# SUP_1_5_3_3.net
KiCad netlist of a schematic drawn in Altium Designer
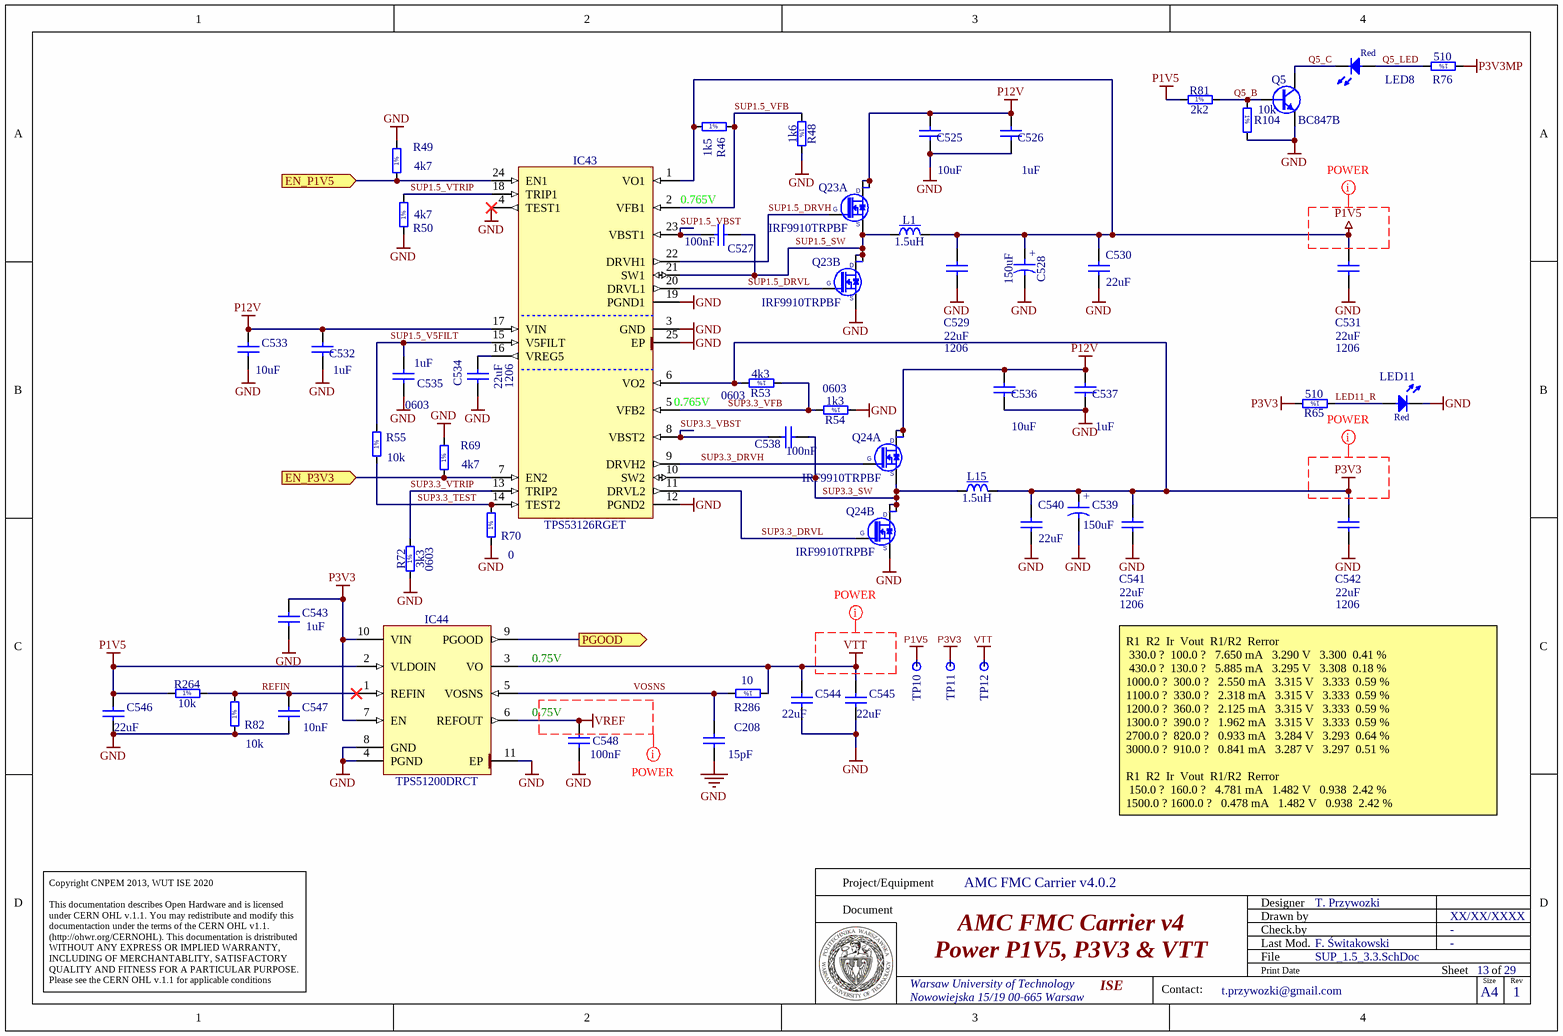
[diagram p0: SUP_1.5_3.3.SchDoc]

(export (version "E")
  (design (tool "Eeschema 10.0.6"))
  (components
    (comp (ref "C208")
      (value "15pF")
      (footprint "CAPC1005X55N")
      (description "Non-polarised capacitor")
      (fields
        (field (name "PART NUMBER") "CC0402_15PF_50V_5%_NP0")
        (field (name "VOLTAGE") "50V")
        (field (name "AUTHOR") "CERN DEM JLC")
      )
      (libsource (lib "Capacitors") (part "Capacitor - non polarized"))
    )
    (comp (ref "C525")
      (value "10uF")
      (footprint "CAPC2012X135N")
      (description "Non-polarised capacitor")
      (fields
        (field (name "PART NUMBER") "CC0805_10UF_16V_10%_X5R")
        (field (name "VOLTAGE") "16V")
        (field (name "AUTHOR") "CERN DEM JLC")
      )
      (libsource (lib "Capacitors") (part "Capacitor - non polarized"))
    )
    (comp (ref "C526")
      (value "1uF")
      (footprint "CAPC1608X87N")
      (description "Non-polarised capacitor")
      (fields
        (field (name "PART NUMBER") "CC0603_1UF_16V_10%_X7R")
        (field (name "VOLTAGE") "16V")
        (field (name "AUTHOR") "CERN DEM JLC")
      )
      (libsource (lib "Capacitors") (part "Capacitor - non polarized"))
    )
    (comp (ref "C527")
      (value "100nF")
      (footprint "CAPC1005X55N")
      (description "Non-polarised capacitor")
      (fields
        (field (name "PART NUMBER") "CC0402_100NF_16V_10%_X7R")
        (field (name "VOLTAGE") "16V")
        (field (name "AUTHOR") "CERN DEM JLC")
      )
      (libsource (lib "Capacitors") (part "Capacitor - non polarized"))
    )
    (comp (ref "C528")
      (value "150uF")
      (footprint "CAPMP7343X200N")
      (description "Polarised capacitor")
      (fields
        (field (name "PART NUMBER") "CAEM7343-20_150UF_4V_20%_LESR0016")
        (field (name "VOLTAGE") "4V")
        (field (name "AUTHOR") "CERN DEM JLC")
      )
      (libsource (lib "Capacitors") (part "Capacitor - polarized"))
    )
    (comp (ref "C529")
      (value "22uF")
      (footprint "CAPC3216X180N")
      (description "Non-polarised capacitor")
      (fields
        (field (name "PART NUMBER") "CC1206_22UF_10V_10%_X7R")
        (field (name "VOLTAGE") "10V")
        (field (name "CASE") "1206")
        (field (name "AUTHOR") "CERN DEM JLC")
      )
      (libsource (lib "Capacitors") (part "Capacitor - non polarized"))
    )
    (comp (ref "C530")
      (value "22uF")
      (footprint "CAPC3216X180N")
      (description "Non-polarised capacitor")
      (fields
        (field (name "PART NUMBER") "CC1206_22UF_10V_10%_X7R")
        (field (name "VOLTAGE") "10V")
        (field (name "AUTHOR") "CERN DEM JLC")
      )
      (libsource (lib "Capacitors") (part "Capacitor - non polarized"))
    )
    (comp (ref "C531")
      (value "22uF")
      (footprint "CAPC3216X180N")
      (description "Non-polarised capacitor")
      (fields
        (field (name "PART NUMBER") "CC1206_22UF_10V_10%_X7R")
        (field (name "VOLTAGE") "10V")
        (field (name "CASE") "1206")
        (field (name "AUTHOR") "CERN DEM JLC")
      )
      (libsource (lib "Capacitors") (part "Capacitor - non polarized"))
    )
    (comp (ref "C532")
      (value "1uF")
      (footprint "CAPC1608X87N")
      (description "Non-polarised capacitor")
      (fields
        (field (name "PART NUMBER") "CC0603_1UF_16V_10%_X7R")
        (field (name "VOLTAGE") "16V")
        (field (name "AUTHOR") "CERN DEM JLC")
      )
      (libsource (lib "Capacitors") (part "Capacitor - non polarized"))
    )
    (comp (ref "C533")
      (value "10uF")
      (footprint "CAPC2012X135N")
      (description "Non-polarised capacitor")
      (fields
        (field (name "PART NUMBER") "CC0805_10UF_16V_10%_X5R")
        (field (name "VOLTAGE") "16V")
        (field (name "AUTHOR") "CERN DEM JLC")
      )
      (libsource (lib "Capacitors") (part "Capacitor - non polarized"))
    )
    (comp (ref "C534")
      (value "22uF")
      (footprint "CAPC3216X180N")
      (description "Non-polarised capacitor")
      (fields
        (field (name "PART NUMBER") "CC1206_22UF_10V_10%_X7R")
        (field (name "VOLTAGE") "10V")
        (field (name "CASE") "1206")
        (field (name "AUTHOR") "CERN DEM JLC")
      )
      (libsource (lib "Capacitors") (part "Capacitor - non polarized"))
    )
    (comp (ref "C535")
      (value "1uF")
      (footprint "CAPC1608X87N")
      (description "Non-polarised capacitor")
      (fields
        (field (name "PART NUMBER") "CC0603_1UF_16V_10%_X7R")
        (field (name "VOLTAGE") "16V")
        (field (name "CASE") "0603")
        (field (name "AUTHOR") "CERN DEM JLC")
      )
      (libsource (lib "Capacitors") (part "Capacitor - non polarized"))
    )
    (comp (ref "C536")
      (value "10uF")
      (footprint "CAPC2012X135N")
      (description "Non-polarised capacitor")
      (fields
        (field (name "PART NUMBER") "CC0805_10UF_16V_10%_X5R")
        (field (name "VOLTAGE") "16V")
        (field (name "AUTHOR") "CERN DEM JLC")
      )
      (libsource (lib "Capacitors") (part "Capacitor - non polarized"))
    )
    (comp (ref "C537")
      (value "1uF")
      (footprint "CAPC1608X87N")
      (description "Non-polarised capacitor")
      (fields
        (field (name "PART NUMBER") "CC0603_1UF_16V_10%_X7R")
        (field (name "VOLTAGE") "16V")
        (field (name "AUTHOR") "CERN DEM JLC")
      )
      (libsource (lib "Capacitors") (part "Capacitor - non polarized"))
    )
    (comp (ref "C538")
      (value "100nF")
      (footprint "CAPC1005X55N")
      (description "Non-polarised capacitor")
      (fields
        (field (name "PART NUMBER") "CC0402_100NF_16V_10%_X7R")
        (field (name "VOLTAGE") "16V")
        (field (name "AUTHOR") "CERN DEM JLC")
      )
      (libsource (lib "Capacitors") (part "Capacitor - non polarized"))
    )
    (comp (ref "C539")
      (value "150uF")
      (footprint "CAPMP7343X200N")
      (description "Polarised capacitor")
      (fields
        (field (name "PART NUMBER") "CAEM7343-20_150UF_4V_20%_LESR0016")
        (field (name "VOLTAGE") "4V")
        (field (name "AUTHOR") "CERN DEM JLC")
      )
      (libsource (lib "Capacitors") (part "Capacitor - polarized"))
    )
    (comp (ref "C540")
      (value "22uF")
      (footprint "CAPC3216X180N")
      (description "Non-polarised capacitor")
      (fields
        (field (name "PART NUMBER") "CC1206_22UF_10V_10%_X7R")
        (field (name "VOLTAGE") "10V")
        (field (name "AUTHOR") "CERN DEM JLC")
      )
      (libsource (lib "Capacitors") (part "Capacitor - non polarized"))
    )
    (comp (ref "C541")
      (value "22uF")
      (footprint "CAPC3216X180N")
      (description "Non-polarised capacitor")
      (fields
        (field (name "PART NUMBER") "CC1206_22UF_10V_10%_X7R")
        (field (name "VOLTAGE") "10V")
        (field (name "CASE") "1206")
        (field (name "AUTHOR") "CERN DEM JLC")
      )
      (libsource (lib "Capacitors") (part "Capacitor - non polarized"))
    )
    (comp (ref "C542")
      (value "22uF")
      (footprint "CAPC3216X180N")
      (description "Non-polarised capacitor")
      (fields
        (field (name "PART NUMBER") "CC1206_22UF_10V_10%_X7R")
        (field (name "VOLTAGE") "10V")
        (field (name "CASE") "1206")
        (field (name "AUTHOR") "CERN DEM JLC")
      )
      (libsource (lib "Capacitors") (part "Capacitor - non polarized"))
    )
    (comp (ref "C543")
      (value "1uF")
      (footprint "CAPC1608X87N")
      (description "Non-polarised capacitor")
      (fields
        (field (name "PART NUMBER") "CC0603_1UF_16V_10%_X7R")
        (field (name "VOLTAGE") "16V")
        (field (name "AUTHOR") "CERN DEM JLC")
      )
      (libsource (lib "Capacitors") (part "Capacitor - non polarized"))
    )
    (comp (ref "C544")
      (value "22uF")
      (footprint "CAPC3216X180N")
      (description "Non-polarised capacitor")
      (fields
        (field (name "PART NUMBER") "CC1206_22UF_10V_10%_X7R")
        (field (name "VOLTAGE") "10V")
        (field (name "AUTHOR") "CERN DEM JLC")
      )
      (libsource (lib "Capacitors") (part "Capacitor - non polarized"))
    )
    (comp (ref "C545")
      (value "22uF")
      (footprint "CAPC3216X180N")
      (description "Non-polarised capacitor")
      (fields
        (field (name "PART NUMBER") "CC1206_22UF_10V_10%_X7R")
        (field (name "VOLTAGE") "10V")
        (field (name "AUTHOR") "CERN DEM JLC")
      )
      (libsource (lib "Capacitors") (part "Capacitor - non polarized"))
    )
    (comp (ref "C546")
      (value "22uF")
      (footprint "CAPC3216X180N")
      (description "Non-polarised capacitor")
      (fields
        (field (name "PART NUMBER") "CC1206_22UF_10V_10%_X7R")
        (field (name "VOLTAGE") "10V")
        (field (name "AUTHOR") "CERN DEM JLC")
      )
      (libsource (lib "Capacitors") (part "Capacitor - non polarized"))
    )
    (comp (ref "C547")
      (value "10nF")
      (footprint "CAPC1005X55N")
      (description "Non-polarised capacitor")
      (fields
        (field (name "PART NUMBER") "CC0402_10NF_16V_10%_X7R")
        (field (name "VOLTAGE") "16V")
        (field (name "AUTHOR") "CERN DEM JLC")
      )
      (libsource (lib "Capacitors") (part "Capacitor - non polarized"))
    )
    (comp (ref "C548")
      (value "100nF")
      (footprint "CAPC0603X33N")
      (description "Non-polarised capacitor")
      (fields
        (field (name "PART NUMBER") "CC0201_100NF_6.3V_10%_X5R")
        (field (name "VOLTAGE") "6.3V")
        (field (name "AUTHOR") "CERN DEM JLC")
      )
      (libsource (lib "Capacitors") (part "Capacitor - non polarized"))
    )
    (comp (ref "IC43")
      (value "TPS53126RGET")
      (footprint "QFN50P400X400X100-25N-S255")
      (description "Dual Synchronous Step-Down Controller For Low Voltage Power Rails")
      (fields (field (name "MANUFACTURER") "TEXAS INSTRUMENTS") (field (name "AUTHOR") "CERN DEM JLC"))
      (libsource (lib "ICs And Semiconductors") (part "TPS53126RGET"))
    )
    (comp (ref "IC44")
      (value "TPS51200DRCT")
      (footprint "SON50P300X300X100-11N-R175X250")
      (description "Sink/Source DDR Termination Regulator")
      (fields (field (name "MANUFACTURER") "TEXAS INSTRUMENTS") (field (name "AUTHOR") "CERN DEM JLC"))
      (libsource (lib "ICs And Semiconductors") (part "TPS51200DRC"))
    )
    (comp (ref "L1")
      (value "1.5uH")
      (footprint "IND_TDK_SPM6530")
      (description "Inductor With Core")
      (fields
        (field (name "PART NUMBER") "IND_1.5UH_20%_TDK_SPM6530")
        (field (name "POWER") "11A")
        (field (name "AUTHOR") "CERN DEM MR")
      )
      (libsource (lib "Inductors & Transformers") (part "Inductor With Magnetic core"))
    )
    (comp (ref "L15")
      (value "1.5uH")
      (footprint "IND_TDK_SPM6530")
      (description "Inductor With Core")
      (fields
        (field (name "PART NUMBER") "IND_1.5UH_20%_TDK_SPM6530")
        (field (name "POWER") "11A")
        (field (name "AUTHOR") "CERN DEM MR")
      )
      (libsource (lib "Inductors & Transformers") (part "Inductor With Magnetic core"))
    )
    (comp (ref "LED8")
      (value "Red")
      (footprint "LED_KINGBRIGHT_KPH-1608SURCK")
      (description "LED Red 1C 2A")
      (fields
        (field (name "PART NUMBER") "LED_KINGBRIGHT_KPH-1608SURCK")
        (field (name "MANUFACTURER") "KINGBRIGHT")
        (field (name "AUTHOR") "CERN DEM JLC")
      )
      (libsource (lib "ICs And Semiconductors") (part "LED Red 1C 2A"))
    )
    (comp (ref "LED11")
      (value "Red")
      (footprint "LED_KINGBRIGHT_KPH-1608SURCK")
      (description "LED Red 1C 2A")
      (fields
        (field (name "PART NUMBER") "LED_KINGBRIGHT_KPH-1608SURCK")
        (field (name "MANUFACTURER") "KINGBRIGHT")
        (field (name "AUTHOR") "CERN DEM JLC")
      )
      (libsource (lib "ICs And Semiconductors") (part "LED Red 1C 2A"))
    )
    (comp (ref "Q5")
      (value "BC847B")
      (footprint "SOT95P230X110-3N")
      (description "NPN Transistor")
      (fields (field (name "MANUFACTURER") "NXP SEMICONDUCTORS") (field (name "AUTHOR") "CERN DEM JLC"))
      (libsource (lib "ICs And Semiconductors") (part "NPN B1 E2 C3"))
    )
    (comp (ref "Q23")
      (value "IRF9910TRPBF")
      (footprint "SOIC127P600X175-8N")
      (description "Dual SO-8 MOSFET For POL Cconverter")
      (fields (field (name "MANUFACTURER") "INTERNATIONAL RECTIFIER") (field (name "AUTHOR") "TP"))
      (libsource (lib "AMC_FMC_Carrier") (part "IRF9910"))
    )
    (comp (ref "Q24")
      (value "IRF9910TRPBF")
      (footprint "SOIC127P600X175-8N")
      (description "Dual SO-8 MOSFET For POL Cconverter")
      (fields (field (name "MANUFACTURER") "INTERNATIONAL RECTIFIER") (field (name "AUTHOR") "TP"))
      (libsource (lib "AMC_FMC_Carrier") (part "IRF9910"))
    )
    (comp (ref "R46")
      (value "1k5")
      (footprint "RESC1608X55N")
      (description "Resistor - 1%")
      (fields
        (field (name "PART NUMBER") "R0603_1K5_1%_0.1W_100PPM")
        (field (name "POWER") "0.1W")
        (field (name "AUTHOR") "CERN DEM JLC")
      )
      (libsource (lib "Resistors") (part "Resistor - 1%"))
    )
    (comp (ref "R48")
      (value "1k6")
      (footprint "RESC1608X55N")
      (description "Resistor - 1%")
      (fields
        (field (name "PART NUMBER") "R0603_1K6_1%_0.1W_100PPM")
        (field (name "POWER") "0.1W")
        (field (name "AUTHOR") "CERN DEM JLC")
      )
      (libsource (lib "Resistors") (part "Resistor - 1%"))
    )
    (comp (ref "R49")
      (value "4k7")
      (footprint "RESC1005X40N")
      (description "Resistor - 1%")
      (fields
        (field (name "PART NUMBER") "R0402_4K7_1%_0.0625W_100PPM")
        (field (name "POWER") "0.0625W")
        (field (name "AUTHOR") "CERN DEM JLC")
      )
      (libsource (lib "Resistors") (part "Resistor - 1%"))
    )
    (comp (ref "R50")
      (value "4k7")
      (footprint "RESC1005X40N")
      (description "Resistor - 1%")
      (fields
        (field (name "PART NUMBER") "R0402_4K7_1%_0.0625W_100PPM")
        (field (name "POWER") "0.0625W")
        (field (name "AUTHOR") "CERN DEM JLC")
      )
      (libsource (lib "Resistors") (part "Resistor - 1%"))
    )
    (comp (ref "R53")
      (value "4k3")
      (footprint "RESC1608X55N")
      (description "Resistor - 1%")
      (fields
        (field (name "PART NUMBER") "R0603_4K3_1%_0.1W_100PPM")
        (field (name "POWER") "0.1W")
        (field (name "CASE") "0603")
        (field (name "AUTHOR") "CERN DEM JLC")
      )
      (libsource (lib "Resistors") (part "Resistor - 1%"))
    )
    (comp (ref "R54")
      (value "1k3")
      (footprint "RESC1608X55N")
      (description "Resistor - 1%")
      (fields
        (field (name "PART NUMBER") "R0603_1K3_1%_0.1W_100PPM")
        (field (name "POWER") "0.1W")
        (field (name "CASE") "0603")
        (field (name "AUTHOR") "CERN DEM JLC")
      )
      (libsource (lib "Resistors") (part "Resistor - 1%"))
    )
    (comp (ref "R55")
      (value "10k")
      (footprint "RESC1005X40N")
      (description "Resistor - 1%")
      (fields
        (field (name "PART NUMBER") "R0402_10K_1%_0.0625W_100PPM")
        (field (name "POWER") "0.0625W")
        (field (name "AUTHOR") "CERN DEM JLC")
      )
      (libsource (lib "Resistors") (part "Resistor - 1%"))
    )
    (comp (ref "R65")
      (value "510")
      (footprint "RESC1005X40N")
      (description "Resistor - 1%")
      (fields
        (field (name "PART NUMBER") "R0402_510R_1%_0.0625W_100PPM")
        (field (name "POWER") "0.0625W")
        (field (name "AUTHOR") "CERN DEM JLC")
      )
      (libsource (lib "Resistors") (part "Resistor - 1%"))
    )
    (comp (ref "R69")
      (value "4k7")
      (footprint "RESC1005X40N")
      (description "Resistor - 1%")
      (fields
        (field (name "PART NUMBER") "R0402_4K7_1%_0.0625W_100PPM")
        (field (name "POWER") "0.0625W")
        (field (name "AUTHOR") "CERN DEM JLC")
      )
      (libsource (lib "Resistors") (part "Resistor - 1%"))
    )
    (comp (ref "R70")
      (value "0")
      (footprint "RESC1005X40N")
      (description "Resistor - 1%")
      (fields
        (field (name "PART NUMBER") "R0402_0R_JUMPER")
        (field (name "MANUFACTURER") "GENERIC")
        (field (name "AUTHOR") "CERN DEM JLC")
      )
      (libsource (lib "Resistors") (part "Resistor - 1%"))
    )
    (comp (ref "R72")
      (value "3k3")
      (footprint "RESC1608X55N")
      (description "Resistor - 1%")
      (fields
        (field (name "PART NUMBER") "R0603_3K3_1%_0.1W_100PPM")
        (field (name "POWER") "0.1W")
        (field (name "CASE") "0603")
        (field (name "AUTHOR") "CERN DEM JLC")
      )
      (libsource (lib "Resistors") (part "Resistor - 1%"))
    )
    (comp (ref "R76")
      (value "510")
      (footprint "RESC1005X40N")
      (description "Resistor - 1%")
      (fields
        (field (name "PART NUMBER") "R0402_510R_1%_0.0625W_100PPM")
        (field (name "POWER") "0.0625W")
        (field (name "AUTHOR") "CERN DEM JLC")
      )
      (libsource (lib "Resistors") (part "Resistor - 1%"))
    )
    (comp (ref "R81")
      (value "2k2")
      (footprint "RESC1005X40N")
      (description "Resistor - 1%")
      (fields
        (field (name "PART NUMBER") "R0402_2K2_1%_0.0625W_100PPM")
        (field (name "POWER") "0.0625W")
        (field (name "AUTHOR") "CERN DEM JLC")
      )
      (libsource (lib "Resistors") (part "Resistor - 1%"))
    )
    (comp (ref "R82")
      (value "10k")
      (footprint "RESC1005X40N")
      (description "Resistor - 1%")
      (fields
        (field (name "PART NUMBER") "R0402_10K_1%_0.0625W_100PPM")
        (field (name "POWER") "0.0625W")
        (field (name "AUTHOR") "CERN DEM JLC")
      )
      (libsource (lib "Resistors") (part "Resistor - 1%"))
    )
    (comp (ref "R104")
      (value "10k")
      (footprint "RESC1005X40N")
      (description "Resistor - 1%")
      (fields
        (field (name "PART NUMBER") "R0402_10K_1%_0.0625W_100PPM")
        (field (name "POWER") "0.0625W")
        (field (name "AUTHOR") "CERN DEM JLC")
      )
      (libsource (lib "Resistors") (part "Resistor - 1%"))
    )
    (comp (ref "R264")
      (value "10k")
      (footprint "RESC1005X40N")
      (description "Resistor - 1%")
      (fields
        (field (name "PART NUMBER") "R0402_10K_1%_0.0625W_100PPM")
        (field (name "POWER") "0.0625W")
        (field (name "AUTHOR") "CERN DEM JLC")
      )
      (libsource (lib "Resistors") (part "Resistor - 1%"))
    )
    (comp (ref "R286")
      (value "10")
      (footprint "RESC1005X40N")
      (description "Resistor - 1%")
      (fields
        (field (name "PART NUMBER") "R0402_10R_1%_0.0625W_200PPM")
        (field (name "POWER") "0.0625W")
        (field (name "AUTHOR") "CERN DEM JLC")
      )
      (libsource (lib "Resistors") (part "Resistor - 1%"))
    )
    (comp (ref "TP10")
      (value "Test Point")
      (footprint "TPS127")
      (fields (field (name "PART NUMBER") "SMD_PAD_1.27X1.27MM") (field (name "AUTHOR") "CERN DEM JLC"))
      (libsource (lib "Eletro-mechanical") (part "Test Point"))
    )
    (comp (ref "TP11")
      (value "Test Point")
      (footprint "TPS127")
      (fields (field (name "PART NUMBER") "SMD_PAD_1.27X1.27MM") (field (name "AUTHOR") "CERN DEM JLC"))
      (libsource (lib "Eletro-mechanical") (part "Test Point"))
    )
    (comp (ref "TP12")
      (value "Test Point")
      (footprint "TPS127")
      (fields (field (name "PART NUMBER") "SMD_PAD_1.27X1.27MM") (field (name "AUTHOR") "CERN DEM JLC"))
      (libsource (lib "Eletro-mechanical") (part "Test Point"))
    )
  )
  (nets
    (net (code "1") (name "/EN_P1V5") (class "Default")
      (node (ref "IC43") (pin "24") (pinfunction "EN1_24") (pintype "input"))
      (node (ref "R49") (pin "1") (pinfunction "1_1") (pintype "passive"))
    )
    (net (code "2") (name "/EN_P3V3") (class "Default")
      (node (ref "IC43") (pin "7") (pinfunction "EN2_7") (pintype "input"))
      (node (ref "R69") (pin "1") (pinfunction "1_1") (pintype "passive"))
    )
    (net (code "3") (name "/LED11_R") (class "Default")
      (node (ref "LED11") (pin "2") (pinfunction "A_2") (pintype "passive"))
      (node (ref "R65") (pin "1") (pinfunction "1_1") (pintype "passive"))
    )
    (net (code "4") (name "/PGOOD") (class "Default")
      (node (ref "IC44") (pin "9") (pinfunction "PGOOD_9") (pintype "output"))
    )
    (net (code "5") (name "/Q5_B") (class "Default")
      (node (ref "Q5") (pin "1") (pinfunction "B_1") (pintype "passive"))
      (node (ref "R104") (pin "1") (pinfunction "1_1") (pintype "passive"))
      (node (ref "R81") (pin "2") (pinfunction "2_2") (pintype "passive"))
    )
    (net (code "6") (name "/Q5_C") (class "Default")
      (node (ref "LED8") (pin "1") (pinfunction "C_1") (pintype "passive"))
      (node (ref "Q5") (pin "3") (pinfunction "C_3") (pintype "passive"))
    )
    (net (code "7") (name "/Q5_LED") (class "Default")
      (node (ref "LED8") (pin "2") (pinfunction "A_2") (pintype "passive"))
      (node (ref "R76") (pin "2") (pinfunction "2_2") (pintype "passive"))
    )
    (net (code "8") (name "/REFIN") (class "Default")
      (node (ref "C547") (pin "2") (pinfunction "2_2") (pintype "passive"))
      (node (ref "IC44") (pin "1") (pinfunction "REFIN_1") (pintype "input"))
      (node (ref "R264") (pin "2") (pinfunction "2_2") (pintype "passive"))
      (node (ref "R82") (pin "2") (pinfunction "2_2") (pintype "passive"))
    )
    (net (code "9") (name "/SUP1.5_DRVH") (class "Default")
      (node (ref "IC43") (pin "22") (pinfunction "DRVH1_22") (pintype "output"))
      (node (ref "Q23") (pin "4") (pinfunction "G_4") (pintype "passive"))
    )
    (net (code "10") (name "/SUP1.5_DRVL") (class "Default")
      (node (ref "IC43") (pin "20") (pinfunction "DRVL1_20") (pintype "output"))
      (node (ref "Q23") (pin "2") (pinfunction "G_2") (pintype "passive"))
    )
    (net (code "11") (name "/SUP1.5_SW") (class "Default")
      (node (ref "C527") (pin "1") (pinfunction "1_1") (pintype "passive"))
      (node (ref "IC43") (pin "21") (pinfunction "SW1_21") (pintype "bidirectional"))
      (node (ref "L1") (pin "1") (pinfunction "1_1") (pintype "passive"))
      (node (ref "Q23") (pin "3") (pinfunction "S_3") (pintype "passive"))
      (node (ref "Q23") (pin "7") (pinfunction "D_7") (pintype "passive"))
      (node (ref "Q23") (pin "8") (pinfunction "D_8") (pintype "passive"))
    )
    (net (code "12") (name "/SUP1.5_V5FILT") (class "Default")
      (node (ref "C535") (pin "2") (pinfunction "2_2") (pintype "passive"))
      (node (ref "IC43") (pin "15") (pinfunction "V5FILT_15") (pintype "input"))
      (node (ref "R55") (pin "2") (pinfunction "2_2") (pintype "passive"))
    )
    (net (code "13") (name "/SUP1.5_VBST") (class "Default")
      (node (ref "C527") (pin "2") (pinfunction "2_2") (pintype "passive"))
      (node (ref "IC43") (pin "23") (pinfunction "VBST1_23") (pintype "input"))
    )
    (net (code "14") (name "/SUP1.5_VFB") (class "Default")
      (node (ref "IC43") (pin "2") (pinfunction "VFB1_2") (pintype "input"))
      (node (ref "R46") (pin "2") (pinfunction "2_2") (pintype "passive"))
      (node (ref "R48") (pin "1") (pinfunction "1_1") (pintype "passive"))
    )
    (net (code "15") (name "/SUP1.5_VTRIP") (class "Default")
      (node (ref "IC43") (pin "18") (pinfunction "TRIP1_18") (pintype "input"))
      (node (ref "R50") (pin "2") (pinfunction "2_2") (pintype "passive"))
    )
    (net (code "16") (name "/SUP3.3_DRVH") (class "Default")
      (node (ref "IC43") (pin "9") (pinfunction "DRVH2_9") (pintype "output"))
      (node (ref "Q24") (pin "4") (pinfunction "G_4") (pintype "passive"))
    )
    (net (code "17") (name "/SUP3.3_DRVL") (class "Default")
      (node (ref "IC43") (pin "11") (pinfunction "DRVL2_11") (pintype "output"))
      (node (ref "Q24") (pin "2") (pinfunction "G_2") (pintype "passive"))
    )
    (net (code "18") (name "/SUP3.3_SW") (class "Default")
      (node (ref "C538") (pin "1") (pinfunction "1_1") (pintype "passive"))
      (node (ref "IC43") (pin "10") (pinfunction "SW2_10") (pintype "bidirectional"))
      (node (ref "L15") (pin "1") (pinfunction "1_1") (pintype "passive"))
      (node (ref "Q24") (pin "3") (pinfunction "S_3") (pintype "passive"))
      (node (ref "Q24") (pin "7") (pinfunction "D_7") (pintype "passive"))
      (node (ref "Q24") (pin "8") (pinfunction "D_8") (pintype "passive"))
    )
    (net (code "19") (name "/SUP3.3_TEST") (class "Default")
      (node (ref "IC43") (pin "14") (pinfunction "TEST2_14") (pintype "input"))
      (node (ref "R55") (pin "1") (pinfunction "1_1") (pintype "passive"))
      (node (ref "R70") (pin "2") (pinfunction "2_2") (pintype "passive"))
    )
    (net (code "20") (name "/SUP3.3_VBST") (class "Default")
      (node (ref "C538") (pin "2") (pinfunction "2_2") (pintype "passive"))
      (node (ref "IC43") (pin "8") (pinfunction "VBST2_8") (pintype "input"))
    )
    (net (code "21") (name "/SUP3.3_VFB") (class "Default")
      (node (ref "IC43") (pin "5") (pinfunction "VFB2_5") (pintype "input"))
      (node (ref "R53") (pin "1") (pinfunction "1_1") (pintype "passive"))
      (node (ref "R54") (pin "2") (pinfunction "2_2") (pintype "passive"))
    )
    (net (code "22") (name "/SUP3.3_VTRIP") (class "Default")
      (node (ref "IC43") (pin "13") (pinfunction "TRIP2_13") (pintype "input"))
      (node (ref "R72") (pin "2") (pinfunction "2_2") (pintype "passive"))
    )
    (net (code "23") (name "/VOSNS") (class "Default")
      (node (ref "C208") (pin "1") (pinfunction "1_1") (pintype "passive"))
      (node (ref "IC44") (pin "5") (pinfunction "VOSNS_5") (pintype "input"))
      (node (ref "R286") (pin "2") (pinfunction "2_2") (pintype "passive"))
    )
    (net (code "24") (name "GND") (class "Default")
      (node (ref "C208") (pin "2") (pinfunction "2_2") (pintype "passive"))
      (node (ref "C525") (pin "1") (pinfunction "1_1") (pintype "passive"))
      (node (ref "C526") (pin "1") (pinfunction "1_1") (pintype "passive"))
      (node (ref "C528") (pin "2") (pinfunction "2_2") (pintype "passive"))
      (node (ref "C529") (pin "2") (pinfunction "2_2") (pintype "passive"))
      (node (ref "C530") (pin "2") (pinfunction "2_2") (pintype "passive"))
      (node (ref "C531") (pin "2") (pinfunction "2_2") (pintype "passive"))
      (node (ref "C532") (pin "1") (pinfunction "1_1") (pintype "passive"))
      (node (ref "C533") (pin "1") (pinfunction "1_1") (pintype "passive"))
      (node (ref "C534") (pin "1") (pinfunction "1_1") (pintype "passive"))
      (node (ref "C535") (pin "1") (pinfunction "1_1") (pintype "passive"))
      (node (ref "C536") (pin "1") (pinfunction "1_1") (pintype "passive"))
      (node (ref "C537") (pin "1") (pinfunction "1_1") (pintype "passive"))
      (node (ref "C539") (pin "2") (pinfunction "2_2") (pintype "passive"))
      (node (ref "C540") (pin "2") (pinfunction "2_2") (pintype "passive"))
      (node (ref "C541") (pin "2") (pinfunction "2_2") (pintype "passive"))
      (node (ref "C542") (pin "2") (pinfunction "2_2") (pintype "passive"))
      (node (ref "C543") (pin "1") (pinfunction "1_1") (pintype "passive"))
      (node (ref "C544") (pin "1") (pinfunction "1_1") (pintype "passive"))
      (node (ref "C545") (pin "1") (pinfunction "1_1") (pintype "passive"))
      (node (ref "C546") (pin "1") (pinfunction "1_1") (pintype "passive"))
      (node (ref "C547") (pin "1") (pinfunction "1_1") (pintype "passive"))
      (node (ref "C548") (pin "1") (pinfunction "1_1") (pintype "passive"))
      (node (ref "IC43") (pin "12") (pinfunction "PGND2_12") (pintype "power_in"))
      (node (ref "IC43") (pin "19") (pinfunction "PGND1_19") (pintype "power_in"))
      (node (ref "IC43") (pin "25") (pinfunction "EP_25") (pintype "power_in"))
      (node (ref "IC43") (pin "3") (pinfunction "GND_3") (pintype "power_in"))
      (node (ref "IC43") (pin "4") (pinfunction "TEST1_4") (pintype "output"))
      (node (ref "IC44") (pin "11") (pinfunction "EP_11") (pintype "power_in"))
      (node (ref "IC44") (pin "4") (pinfunction "PGND_4") (pintype "power_in"))
      (node (ref "IC44") (pin "8") (pinfunction "GND_8") (pintype "power_in"))
      (node (ref "LED11") (pin "1") (pinfunction "C_1") (pintype "passive"))
      (node (ref "Q23") (pin "1") (pinfunction "S_1") (pintype "passive"))
      (node (ref "Q24") (pin "1") (pinfunction "S_1") (pintype "passive"))
      (node (ref "Q5") (pin "2") (pinfunction "E_2") (pintype "passive"))
      (node (ref "R104") (pin "2") (pinfunction "2_2") (pintype "passive"))
      (node (ref "R48") (pin "2") (pinfunction "2_2") (pintype "passive"))
      (node (ref "R49") (pin "2") (pinfunction "2_2") (pintype "passive"))
      (node (ref "R50") (pin "1") (pinfunction "1_1") (pintype "passive"))
      (node (ref "R54") (pin "1") (pinfunction "1_1") (pintype "passive"))
      (node (ref "R69") (pin "2") (pinfunction "2_2") (pintype "passive"))
      (node (ref "R70") (pin "1") (pinfunction "1_1") (pintype "passive"))
      (node (ref "R72") (pin "1") (pinfunction "1_1") (pintype "passive"))
      (node (ref "R82") (pin "1") (pinfunction "1_1") (pintype "passive"))
    )
    (net (code "25") (name "Net-(IC43-VREG5)") (class "Default")
      (node (ref "C534") (pin "2") (pinfunction "2_2") (pintype "passive"))
      (node (ref "IC43") (pin "16") (pinfunction "VREG5_16") (pintype "output"))
    )
    (net (code "26") (name "P1V5") (class "Default")
      (node (ref "C528") (pin "1") (pinfunction "1_1") (pintype "passive"))
      (node (ref "C529") (pin "1") (pinfunction "1_1") (pintype "passive"))
      (node (ref "C530") (pin "1") (pinfunction "1_1") (pintype "passive"))
      (node (ref "C531") (pin "1") (pinfunction "1_1") (pintype "passive"))
      (node (ref "C546") (pin "2") (pinfunction "2_2") (pintype "passive"))
      (node (ref "IC43") (pin "1") (pinfunction "VO1_1") (pintype "input"))
      (node (ref "IC44") (pin "2") (pinfunction "VLDOIN_2") (pintype "input"))
      (node (ref "L1") (pin "2") (pinfunction "2_2") (pintype "passive"))
      (node (ref "R264") (pin "1") (pinfunction "1_1") (pintype "passive"))
      (node (ref "R46") (pin "1") (pinfunction "1_1") (pintype "passive"))
      (node (ref "R81") (pin "1") (pinfunction "1_1") (pintype "passive"))
      (node (ref "TP10") (pin "1") (pinfunction "1_1") (pintype "bidirectional"))
    )
    (net (code "27") (name "P3V3") (class "Default")
      (node (ref "C539") (pin "1") (pinfunction "1_1") (pintype "passive"))
      (node (ref "C540") (pin "1") (pinfunction "1_1") (pintype "passive"))
      (node (ref "C541") (pin "1") (pinfunction "1_1") (pintype "passive"))
      (node (ref "C542") (pin "1") (pinfunction "1_1") (pintype "passive"))
      (node (ref "C543") (pin "2") (pinfunction "2_2") (pintype "passive"))
      (node (ref "IC43") (pin "6") (pinfunction "VO2_6") (pintype "input"))
      (node (ref "IC44") (pin "10") (pinfunction "VIN_10") (pintype "power_in"))
      (node (ref "IC44") (pin "7") (pinfunction "EN_7") (pintype "input"))
      (node (ref "L15") (pin "2") (pinfunction "2_2") (pintype "passive"))
      (node (ref "R53") (pin "2") (pinfunction "2_2") (pintype "passive"))
      (node (ref "R65") (pin "2") (pinfunction "2_2") (pintype "passive"))
      (node (ref "TP11") (pin "1") (pinfunction "1_1") (pintype "bidirectional"))
    )
    (net (code "28") (name "P3V3MP") (class "Default")
      (node (ref "R76") (pin "1") (pinfunction "1_1") (pintype "passive"))
    )
    (net (code "29") (name "P12V") (class "Default")
      (node (ref "C525") (pin "2") (pinfunction "2_2") (pintype "passive"))
      (node (ref "C526") (pin "2") (pinfunction "2_2") (pintype "passive"))
      (node (ref "C532") (pin "2") (pinfunction "2_2") (pintype "passive"))
      (node (ref "C533") (pin "2") (pinfunction "2_2") (pintype "passive"))
      (node (ref "C536") (pin "2") (pinfunction "2_2") (pintype "passive"))
      (node (ref "C537") (pin "2") (pinfunction "2_2") (pintype "passive"))
      (node (ref "IC43") (pin "17") (pinfunction "VIN_17") (pintype "input"))
      (node (ref "Q23") (pin "5") (pinfunction "D_5") (pintype "passive"))
      (node (ref "Q23") (pin "6") (pinfunction "D_6") (pintype "passive"))
      (node (ref "Q24") (pin "5") (pinfunction "D_5") (pintype "passive"))
      (node (ref "Q24") (pin "6") (pinfunction "D_6") (pintype "passive"))
    )
    (net (code "30") (name "VREF") (class "Default")
      (node (ref "C548") (pin "2") (pinfunction "2_2") (pintype "passive"))
      (node (ref "IC44") (pin "6") (pinfunction "REFOUT_6") (pintype "output"))
    )
    (net (code "31") (name "VTT") (class "Default")
      (node (ref "C544") (pin "2") (pinfunction "2_2") (pintype "passive"))
      (node (ref "C545") (pin "2") (pinfunction "2_2") (pintype "passive"))
      (node (ref "IC44") (pin "3") (pinfunction "VO_3") (pintype "power_in"))
      (node (ref "R286") (pin "1") (pinfunction "1_1") (pintype "passive"))
      (node (ref "TP12") (pin "1") (pinfunction "1_1") (pintype "bidirectional"))
    )
  )
)
